# Interface_CAN.net
KiCad netlist of a schematic drawn in Altium Designer
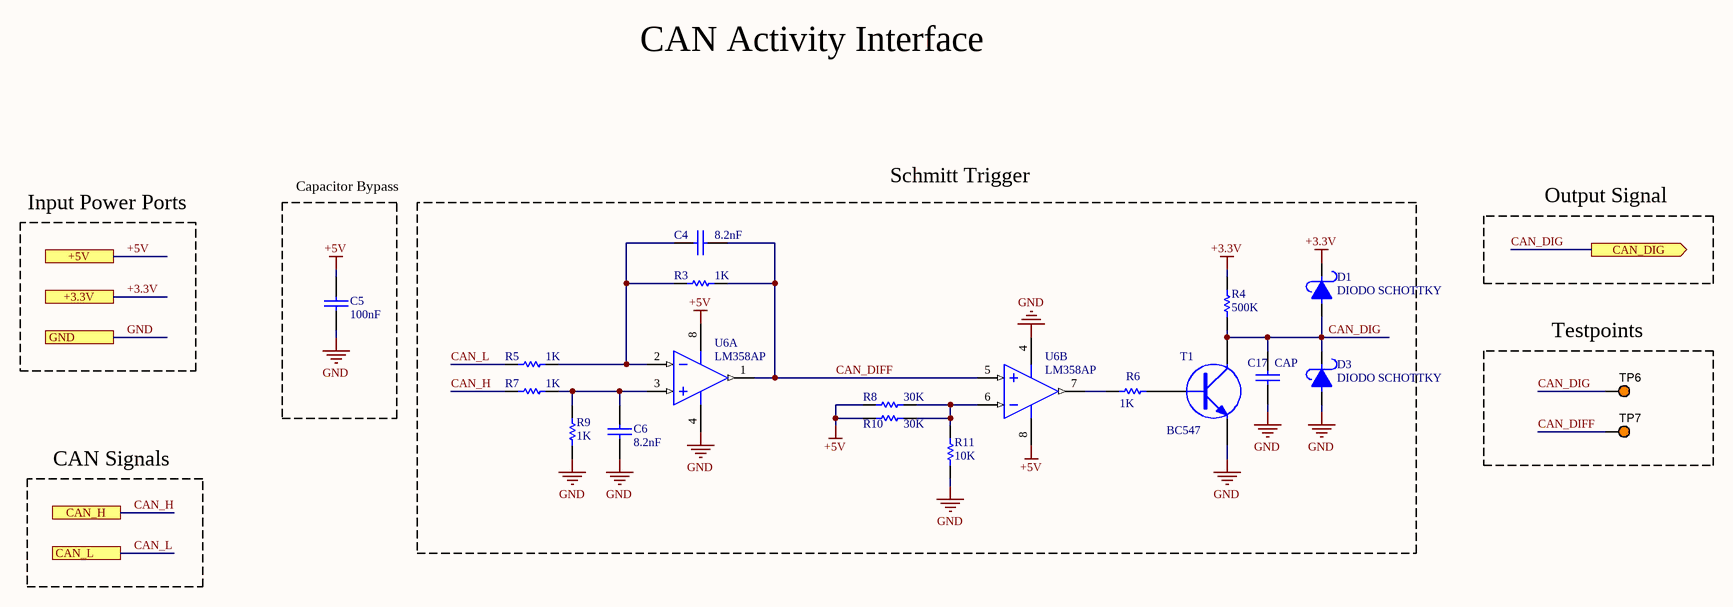
[diagram p0: Interface_CAN.SchDoc]

(export (version "E")
  (design (tool "Eeschema 10.0.6"))
  (components
    (comp (ref "C4") (value "8.2nF") (footprint "CAP200") (libsource (lib "LIBEBAL") (part "CAP")))
    (comp (ref "C5") (value "100nF") (footprint "CAP200") (libsource (lib "LIBEBAL") (part "CAP")))
    (comp (ref "C6") (value "8.2nF") (footprint "CAP200") (libsource (lib "LIBEBAL") (part "CAP")))
    (comp (ref "C17") (value "CAP") (footprint "CAP200") (libsource (lib "LIBEBAL") (part "CAP")))
    (comp (ref "D1")
      (value "DIODO SCHOTTKY")
      (footprint "DO41")
      (libsource (lib "LIBEBAL") (part "DIODO SCHOTTKY"))
    )
    (comp (ref "D3")
      (value "DIODO SCHOTTKY")
      (footprint "DO41")
      (libsource (lib "LIBEBAL") (part "DIODO SCHOTTKY"))
    )
    (comp (ref "R3") (value "1K") (footprint "RES400") (libsource (lib "TD") (part "RES")))
    (comp (ref "R4") (value "500K") (footprint "RES400") (libsource (lib "TD") (part "RES")))
    (comp (ref "R5") (value "1K") (footprint "RES400") (libsource (lib "TD") (part "RES")))
    (comp (ref "R6") (value "1K") (footprint "RES400") (libsource (lib "TD") (part "RES")))
    (comp (ref "R7") (value "1K") (footprint "RES400") (libsource (lib "TD") (part "RES")))
    (comp (ref "R8") (value "30K") (footprint "RES400") (libsource (lib "TD") (part "RES")))
    (comp (ref "R9") (value "1K") (footprint "RES400") (libsource (lib "TD") (part "RES")))
    (comp (ref "R10") (value "30K") (footprint "RES400") (libsource (lib "TD") (part "RES")))
    (comp (ref "R11") (value "10K") (footprint "RES400") (libsource (lib "TD") (part "RES")))
    (comp (ref "T1") (value "BC547") (footprint "TO92") (libsource (lib "TD") (part "TRANSISTOR NPN")))
    (comp (ref "TP6")
      (value "5003")
      (footprint "KSTN-5003")
      (description "Test Point, Orange, Height 4.6 mm, Tail Length 3 mm, 1-Pin THD, RoHS")
      (fields (field (name "MANUFACTURER") "Keystone"))
      (libsource (lib "TD") (part "TESTPOINT_ORANGE"))
    )
    (comp (ref "TP7")
      (value "5003")
      (footprint "KSTN-5003")
      (description "Test Point, Orange, Height 4.6 mm, Tail Length 3 mm, 1-Pin THD, RoHS")
      (fields (field (name "MANUFACTURER") "Keystone"))
      (libsource (lib "TD") (part "TESTPOINT_ORANGE"))
    )
    (comp (ref "U6")
      (value "LM358AP")
      (footprint "P0008A")
      (description "Dual Operational Amplifier, 3 to 32 V, 0 to 70 degC, 8-Pin PDIP (P), Pb-Free (RoHS), Tube")
      (fields (field (name "MANUFACTURER") "Texas Instruments (TI)"))
      (libsource (lib "TD") (part "TI-LM358-8"))
    )
  )
  (nets
    (net (code "1") (name "+3.3V") (class "Default")
      (node (ref "D1") (pin "2") (pinfunction "2_2") (pintype "passive"))
      (node (ref "R4") (pin "2") (pinfunction "2_2") (pintype "passive"))
    )
    (net (code "2") (name "+5V") (class "Default")
      (node (ref "C5") (pin "1") (pinfunction "1_1") (pintype "passive"))
      (node (ref "R10") (pin "1") (pinfunction "1_1") (pintype "passive"))
      (node (ref "R8") (pin "1") (pinfunction "1_1") (pintype "passive"))
      (node (ref "U6") (pin "8") (pinfunction "VCC_8") (pintype "power_in"))
    )
    (net (code "3") (name "/CAN_DIFF") (class "Default")
      (node (ref "C4") (pin "2") (pinfunction "2_2") (pintype "passive"))
      (node (ref "R3") (pin "1") (pinfunction "1_1") (pintype "passive"))
      (node (ref "TP7") (pin "1") (pinfunction "1_1") (pintype "passive"))
      (node (ref "U6") (pin "1") (pinfunction "1OUT_1") (pintype "output"))
      (node (ref "U6") (pin "5") (pinfunction "2IN+_5") (pintype "input"))
    )
    (net (code "4") (name "/CAN_DIG") (class "Default")
      (node (ref "C17") (pin "1") (pinfunction "1_1") (pintype "passive"))
      (node (ref "D1") (pin "1") (pinfunction "1_1") (pintype "passive"))
      (node (ref "D3") (pin "2") (pinfunction "2_2") (pintype "passive"))
      (node (ref "R4") (pin "1") (pinfunction "1_1") (pintype "passive"))
      (node (ref "T1") (pin "2") (pinfunction "C_2") (pintype "passive"))
      (node (ref "TP6") (pin "1") (pinfunction "1_1") (pintype "passive"))
    )
    (net (code "5") (name "/CAN_H") (class "Default")
      (node (ref "R7") (pin "1") (pinfunction "1_1") (pintype "passive"))
    )
    (net (code "6") (name "/CAN_L") (class "Default")
      (node (ref "R5") (pin "1") (pinfunction "1_1") (pintype "passive"))
    )
    (net (code "7") (name "GND") (class "Default")
      (node (ref "C17") (pin "2") (pinfunction "2_2") (pintype "passive"))
      (node (ref "C5") (pin "2") (pinfunction "2_2") (pintype "passive"))
      (node (ref "C6") (pin "2") (pinfunction "2_2") (pintype "passive"))
      (node (ref "D3") (pin "1") (pinfunction "1_1") (pintype "passive"))
      (node (ref "R11") (pin "1") (pinfunction "1_1") (pintype "passive"))
      (node (ref "R9") (pin "1") (pinfunction "1_1") (pintype "passive"))
      (node (ref "T1") (pin "3") (pinfunction "E_3") (pintype "passive"))
      (node (ref "U6") (pin "4") (pinfunction "GND_4") (pintype "power_in"))
    )
    (net (code "8") (name "Net-(T1-B)") (class "Default")
      (node (ref "R6") (pin "2") (pinfunction "2_2") (pintype "passive"))
      (node (ref "T1") (pin "1") (pinfunction "B_1") (pintype "passive"))
    )
    (net (code "9") (name "Net-(U6A-1IN+)") (class "Default")
      (node (ref "C6") (pin "1") (pinfunction "1_1") (pintype "passive"))
      (node (ref "R7") (pin "2") (pinfunction "2_2") (pintype "passive"))
      (node (ref "R9") (pin "2") (pinfunction "2_2") (pintype "passive"))
      (node (ref "U6") (pin "3") (pinfunction "1IN+_3") (pintype "input"))
    )
    (net (code "10") (name "Net-(U6A-1IN-)") (class "Default")
      (node (ref "C4") (pin "1") (pinfunction "1_1") (pintype "passive"))
      (node (ref "R3") (pin "2") (pinfunction "2_2") (pintype "passive"))
      (node (ref "R5") (pin "2") (pinfunction "2_2") (pintype "passive"))
      (node (ref "U6") (pin "2") (pinfunction "1IN-_2") (pintype "input"))
    )
    (net (code "11") (name "Net-(U6B-2IN-)") (class "Default")
      (node (ref "R10") (pin "2") (pinfunction "2_2") (pintype "passive"))
      (node (ref "R11") (pin "2") (pinfunction "2_2") (pintype "passive"))
      (node (ref "R8") (pin "2") (pinfunction "2_2") (pintype "passive"))
      (node (ref "U6") (pin "6") (pinfunction "2IN-_6") (pintype "input"))
    )
    (net (code "12") (name "Net-(U6B-2OUT)") (class "Default")
      (node (ref "R6") (pin "1") (pinfunction "1_1") (pintype "passive"))
      (node (ref "U6") (pin "7") (pinfunction "2OUT_7") (pintype "output"))
    )
  )
)
